# Regulator_9V0_to_5V0.net
KiCad netlist of a schematic drawn in Altium Designer
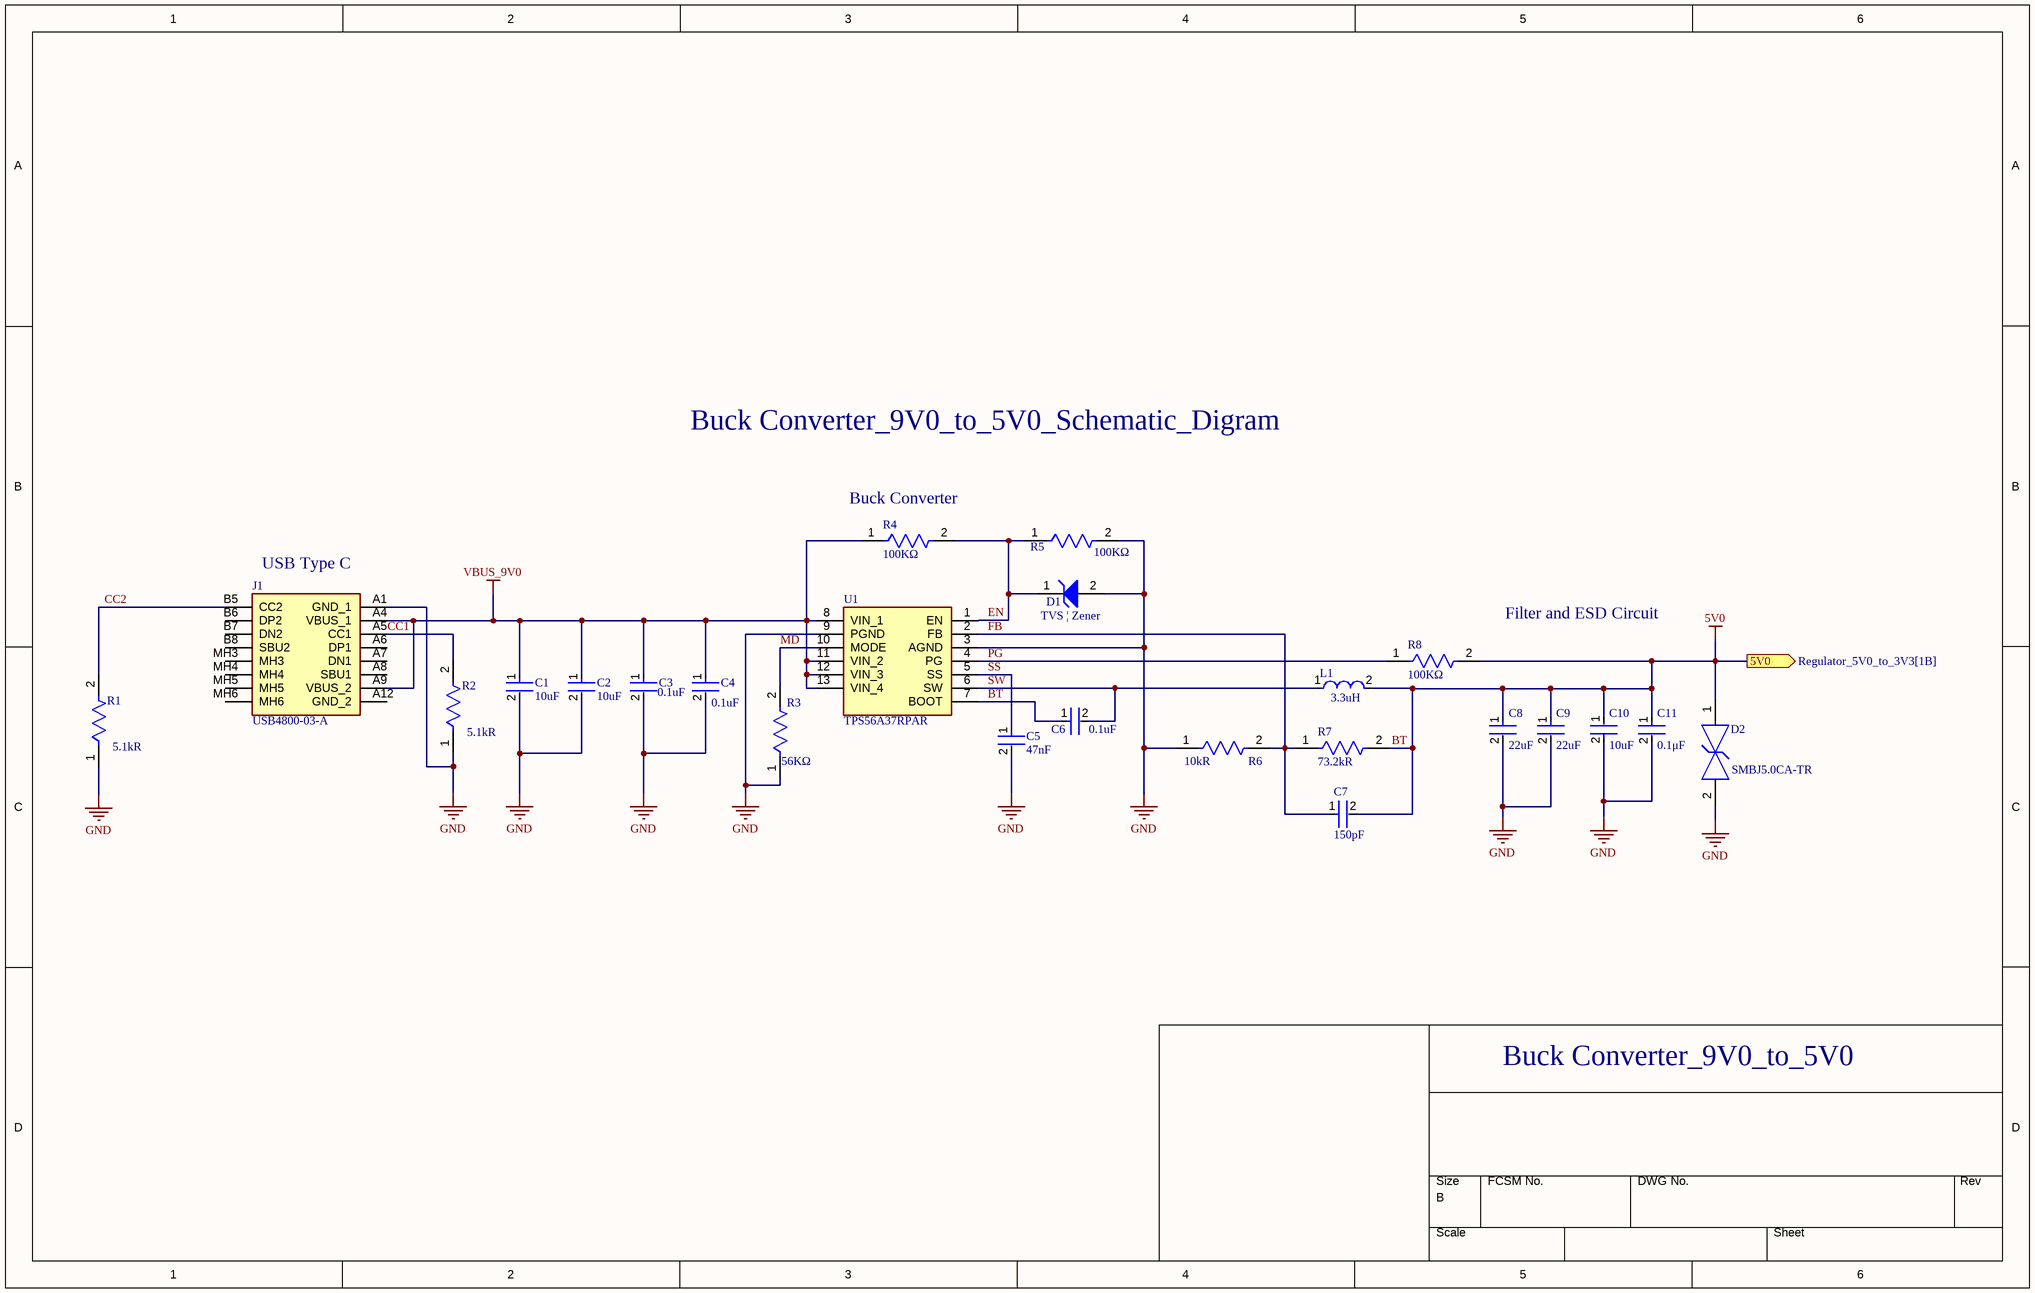
[diagram p0: Regulator_9V0_to_5V0.SchDoc]

(export (version "E")
  (design (tool "Eeschema 10.0.6"))
  (components
    (comp (ref "C1")
      (value "CL21A106KOQNNNG")
      (footprint "FP-CL21-IPC_C")
      (description "CL21 Series 0805 10uF 16V ±10% Tolerance X5R Multilayer Ceramic Chip Capacitor")
      (fields
        (field (name "CAPACITANCE") "10uF")
        (field (name "TOLERANCE") "10%")
        (field (name "VOLTAGE") "16V")
      )
      (libsource (lib "Altium Content Vault") (part "b4654b650e69147ec39a6b967a45e02"))
    )
    (comp (ref "C2")
      (value "CL21A106KOQNNNG")
      (footprint "FP-CL21-IPC_C")
      (description "CL21 Series 0805 10uF 16V ±10% Tolerance X5R Multilayer Ceramic Chip Capacitor")
      (fields
        (field (name "CAPACITANCE") "10uF")
        (field (name "TOLERANCE") "10%")
        (field (name "VOLTAGE") "16V")
      )
      (libsource (lib "Altium Content Vault") (part "b4654b650e69147ec39a6b967a45e02"))
    )
    (comp (ref "C3")
      (value "0402YD104KAT2A")
      (footprint "FP-0402-L_1_0_1-W_0_5_0_1-IPC_B")
      (description "General Purpose Ceramic Capacitor, 0402, 10uF, 10%, X5R, 15%, 16V")
      (fields
        (field (name "VOLTAGE") "16V")
        (field (name "TOLERANCE") "10%")
        (field (name "CAPACITANCE") "0.1uF")
      )
      (libsource (lib "Altium Content Vault") (part "b4654b650e69147ec39a6b967a45e02"))
    )
    (comp (ref "C4")
      (value "0402YD104KAT2A")
      (footprint "FP-0402-L_1_0_1-W_0_5_0_1-IPC_B")
      (description "General Purpose Ceramic Capacitor, 0402, 10uF, 10%, X5R, 15%, 16V")
      (fields
        (field (name "VOLTAGE") "16V")
        (field (name "TOLERANCE") "10%")
        (field (name "CAPACITANCE") "0.1uF")
      )
      (libsource (lib "Altium Content Vault") (part "b4654b650e69147ec39a6b967a45e02"))
    )
    (comp (ref "C5")
      (value "CL05B473KO5NNNC")
      (footprint "FP-CL579-IPC_C")
      (description "Cap Ceramic 47nF 16V X7R ±10% SMD 0402 +125°C Paper T/R")
      (fields
        (field (name "VOLTAGE") "16V")
        (field (name "CAPACITANCE") "47nF")
        (field (name "TOLERANCE") "10%")
      )
      (libsource (lib "Altium Content Vault") (part "b4654b650e69147ec39a6b967a45e02"))
    )
    (comp (ref "C6")
      (value "0402YD104KAT2A")
      (footprint "FP-0402-L_1_0_1-W_0_5_0_1-IPC_B")
      (description "General Purpose Ceramic Capacitor, 0402, 10uF, 10%, X5R, 15%, 16V")
      (fields
        (field (name "VOLTAGE") "16V")
        (field (name "TOLERANCE") "10%")
        (field (name "CAPACITANCE") "0.1uF")
      )
      (libsource (lib "Altium Content Vault") (part "b4654b650e69147ec39a6b967a45e02"))
    )
    (comp (ref "C7")
      (value "C1005NP01H151J050BA")
      (footprint "FP-C1005-050-0_05-IPC_B")
      (description "Multilayer Ceramic Capacitors 150pF ±5% 50V NP0 SMD 0402")
      (fields (field (name "CAPACITANCE") "150pF") (field (name "TOLERANCE") "5%"))
      (libsource (lib "Altium Content Vault") (part "b4654b650e69147ec39a6b967a45e02"))
    )
    (comp (ref "C8")
      (value "CL10A226MO7JZNC")
      (footprint "FP-CL10-IPC_B")
      (description "Cap Ceramic 22uF 16V X5R ±20% Pad SMD 0603 +85°C T/R")
      (fields (field (name "CAPACITANCE") "22uF") (field (name "TOLERANCE") "20%"))
      (libsource (lib "Altium Content Vault") (part "b4654b650e69147ec39a6b967a45e02"))
    )
    (comp (ref "C9")
      (value "CL10A226MO7JZNC")
      (footprint "FP-CL10-IPC_B")
      (description "Cap Ceramic 22uF 16V X5R ±20% Pad SMD 0603 +85°C T/R")
      (fields (field (name "CAPACITANCE") "22uF") (field (name "TOLERANCE") "20%"))
      (libsource (lib "Altium Content Vault") (part "b4654b650e69147ec39a6b967a45e02"))
    )
    (comp (ref "C10")
      (value "C1608X5R1A106M080AC")
      (footprint "FP-C1608-080-0_1-IPC_A")
      (description "Multilayer Ceramic Capacitors 10μF ±20% 10V X5R SMD 0603")
      (fields (field (name "CAPACITANCE") "10uF") (field (name "TOLERANCE") "20%"))
      (libsource (lib "Altium Content Vault") (part "236180d848d6139a670b325ea6854c9"))
    )
    (comp (ref "C11")
      (value "C0603C104K8RACTU")
      (footprint "FP-C0603C-CF-MFG")
      (description "CAP CER 0.1UF 10V X7R 0603")
      (fields
        (field (name "TOLERANCE") "0.1")
        (field (name "OCTOPART") "https://octopart.com/c0603c104k8ractu-kemet-145075")
        (field (name "CAPACITANCE") "0.1μF")
      )
      (libsource (lib "Altium Content Vault") (part "b4654b650e69147ec39a6b967a45e02"))
    )
    (comp (ref "D1")
      (value "ESD5Z6.0T1G")
      (footprint "ONSC-SOD-523-2-502-01_V")
      (fields (field (name "MANUFACTURER") "On Semiconductor"))
      (libsource (lib "Altium Content Vault") (part "ONSC-K1A2-2"))
    )
    (comp (ref "D2")
      (value "SMBJ5.0CA-TR")
      (footprint "FP-SMB-CA-MFG")
      (description "TVS DIODE 5V 13.4V SMB")
      (fields
        (field (name "MANUFACTURER") "STMicroelectronics")
        (field (name "OCTOPART") "https://octopart.com/smbj5.0ca-tr-stmicroelectronics-347080")
      )
      (libsource (lib "Altium Content Vault") (part "876f4347bf90aa6f500f43e3cd03972"))
    )
    (comp (ref "J1")
      (value "USB4800-03-A")
      (footprint "USB480003A")
      (description "Connector")
      (fields (field (name "MOUSER PART NUMBER") "640-USB4800-03-A"))
      (libsource (lib "USB480003A") (part "USB4800-03-A"))
    )
    (comp (ref "L1")
      (value "IHLP2020CZER3R3M11")
      (footprint "FP-IHLP-2020CZ-FP_1_905x2-MFG")
      (description "Fixed Inductors Commercial Low DCR Series 3.3uH 5.5A 40.4mΩ 20%")
      (fields (field (name "INDUCTANCE") "3.3uH") (field (name "TOLERANCE") "20%"))
      (libsource (lib "Altium Content Vault") (part "725321dda6339637d4d059423bc1c3c"))
    )
    (comp (ref "R1")
      (value "CRCW04025K10FKED")
      (footprint "FP-CRCW0402-e3-IPC_C")
      (description "RES Thick Film, 5.1kΩ, 1%, 0.063W, 100ppm/°C, 0402")
      (fields (field (name "TOLERANCE") "1%") (field (name "RESISTANCE") "5.1kR"))
      (libsource (lib "Altium Content Vault") (part "1029c3af85768c4190bb7ad29bc67b5"))
    )
    (comp (ref "R2")
      (value "CRCW04025K10FKED")
      (footprint "FP-CRCW0402-e3-IPC_C")
      (description "RES Thick Film, 5.1kΩ, 1%, 0.063W, 100ppm/°C, 0402")
      (fields (field (name "TOLERANCE") "1%") (field (name "RESISTANCE") "5.1kR"))
      (libsource (lib "Altium Content Vault") (part "1029c3af85768c4190bb7ad29bc67b5"))
    )
    (comp (ref "R3")
      (value "CRGCQ0402F56K")
      (footprint "FP-CRGCQ0402-IPC_C")
      (description "CRGCQ 0402 56K 1%")
      (fields
        (field (name "OCTOPART") "https://octopart.com/crgcq0402f56k-te+connectivity-91017978")
        (field (name "RESISTANCE") "56KΩ")
        (field (name "MANUFACTURER") "TE Connectivity")
      )
      (libsource (lib "Altium Content Vault") (part "1029c3af85768c4190bb7ad29bc67b5"))
    )
    (comp (ref "R4")
      (value "CRGP0402F100K")
      (footprint "FP-CRGP0402-IPC_C")
      (description "SMD Precision Pulse Thick Film Chip Resistor")
      (fields
        (field (name "OCTOPART") "https://octopart.com/crgp0402f100k-te+connectivity-91018658")
        (field (name "TOLERANCE") "0.01")
        (field (name "RESISTANCE") "100KΩ")
      )
      (libsource (lib "Altium Content Vault") (part "1029c3af85768c4190bb7ad29bc67b5"))
    )
    (comp (ref "R5")
      (value "CRGP0402F100K")
      (footprint "FP-CRGP0402-IPC_C")
      (description "SMD Precision Pulse Thick Film Chip Resistor")
      (fields
        (field (name "OCTOPART") "https://octopart.com/crgp0402f100k-te+connectivity-91018658")
        (field (name "TOLERANCE") "0.01")
        (field (name "RESISTANCE") "100KΩ")
      )
      (libsource (lib "Altium Content Vault") (part "1029c3af85768c4190bb7ad29bc67b5"))
    )
    (comp (ref "R6")
      (value "AC0402FR-0710KL")
      (footprint "FP-AC0402-MFG")
      (description "RES 10kΩ ±1% 0.063W 0402")
      (fields (field (name "TOLERANCE") "1%") (field (name "RESISTANCE") "10kR"))
      (libsource (lib "Altium Content Vault") (part "1029c3af85768c4190bb7ad29bc67b5"))
    )
    (comp (ref "R7")
      (value "RC1005F7322CS")
      (footprint "FP-RC1005-IPC_B")
      (description "Res Thick Film 0402 73.2kΩ 1% 0.063W ±100ppm/°C Molded SMD T/R")
      (fields (field (name "TOLERANCE") "1%") (field (name "RESISTANCE") "73.2kR"))
      (libsource (lib "Altium Content Vault") (part "1029c3af85768c4190bb7ad29bc67b5"))
    )
    (comp (ref "R8")
      (value "CRGP0402F100K")
      (footprint "FP-CRGP0402-IPC_C")
      (description "SMD Precision Pulse Thick Film Chip Resistor")
      (fields
        (field (name "OCTOPART") "https://octopart.com/crgp0402f100k-te+connectivity-91018658")
        (field (name "TOLERANCE") "0.01")
        (field (name "RESISTANCE") "100KΩ")
      )
      (libsource (lib "Altium Content Vault") (part "1029c3af85768c4190bb7ad29bc67b5"))
    )
    (comp (ref "U1")
      (value "TPS56A37RPAR")
      (footprint "TPS56A37RPAR")
      (description "Integrated Circuit")
      (fields (field (name "MOUSER PART NUMBER") "595-TPS56A37RPAR"))
      (libsource (lib "TPS56A37RPAR") (part "TPS56A37RPAR"))
    )
  )
  (nets
    (net (code "1") (name "/CC1") (class "Default")
      (node (ref "J1") (pin "A5") (pinfunction "CC1_A5") (pintype "passive"))
      (node (ref "R2") (pin "2") (pinfunction "2_2") (pintype "passive"))
    )
    (net (code "2") (name "/CC2") (class "Default")
      (node (ref "J1") (pin "B5") (pinfunction "CC2_B5") (pintype "passive"))
      (node (ref "R1") (pin "2") (pinfunction "2_2") (pintype "passive"))
    )
    (net (code "3") (name "/EN") (class "Default")
      (node (ref "D1") (pin "1") (pinfunction "K_1") (pintype "passive"))
      (node (ref "R4") (pin "2") (pinfunction "2_2") (pintype "passive"))
      (node (ref "R5") (pin "1") (pinfunction "1_1") (pintype "passive"))
      (node (ref "U1") (pin "1") (pinfunction "EN_1") (pintype "passive"))
    )
    (net (code "4") (name "/FB") (class "Default")
      (node (ref "C7") (pin "1") (pinfunction "1_1") (pintype "passive"))
      (node (ref "R6") (pin "2") (pinfunction "2_2") (pintype "passive"))
      (node (ref "R7") (pin "1") (pinfunction "1_1") (pintype "passive"))
      (node (ref "U1") (pin "2") (pinfunction "FB_2") (pintype "passive"))
    )
    (net (code "5") (name "/MD") (class "Default")
      (node (ref "R3") (pin "2") (pinfunction "2_2") (pintype "passive"))
      (node (ref "U1") (pin "10") (pinfunction "MODE_10") (pintype "passive"))
    )
    (net (code "6") (name "/PG") (class "Default")
      (node (ref "R8") (pin "1") (pinfunction "1_1") (pintype "passive"))
      (node (ref "U1") (pin "4") (pinfunction "PG_4") (pintype "passive"))
    )
    (net (code "7") (name "/SS") (class "Default")
      (node (ref "C5") (pin "1") (pinfunction "1_1") (pintype "passive"))
      (node (ref "U1") (pin "5") (pinfunction "SS_5") (pintype "passive"))
    )
    (net (code "8") (name "/SW") (class "Default")
      (node (ref "C6") (pin "2") (pinfunction "2_2") (pintype "passive"))
      (node (ref "L1") (pin "1") (pinfunction "1_1") (pintype "passive"))
      (node (ref "U1") (pin "6") (pinfunction "SW_6") (pintype "passive"))
    )
    (net (code "9") (name "5V0") (class "Default")
      (node (ref "C10") (pin "1") (pinfunction "1_1") (pintype "passive"))
      (node (ref "C11") (pin "1") (pinfunction "1_1") (pintype "passive"))
      (node (ref "C6") (pin "1") (pinfunction "1_1") (pintype "passive"))
      (node (ref "C7") (pin "2") (pinfunction "2_2") (pintype "passive"))
      (node (ref "C8") (pin "1") (pinfunction "1_1") (pintype "passive"))
      (node (ref "C9") (pin "1") (pinfunction "1_1") (pintype "passive"))
      (node (ref "D2") (pin "1") (pinfunction "1_1") (pintype "passive"))
      (node (ref "L1") (pin "2") (pinfunction "2_2") (pintype "passive"))
      (node (ref "R7") (pin "2") (pinfunction "2_2") (pintype "passive"))
      (node (ref "R8") (pin "2") (pinfunction "2_2") (pintype "passive"))
      (node (ref "U1") (pin "7") (pinfunction "BOOT_7") (pintype "passive"))
    )
    (net (code "10") (name "GND") (class "Default")
      (node (ref "C1") (pin "2") (pinfunction "2_2") (pintype "passive"))
      (node (ref "C10") (pin "2") (pinfunction "2_2") (pintype "passive"))
      (node (ref "C11") (pin "2") (pinfunction "2_2") (pintype "passive"))
      (node (ref "C2") (pin "2") (pinfunction "2_2") (pintype "passive"))
      (node (ref "C3") (pin "2") (pinfunction "2_2") (pintype "passive"))
      (node (ref "C4") (pin "2") (pinfunction "2_2") (pintype "passive"))
      (node (ref "C5") (pin "2") (pinfunction "2_2") (pintype "passive"))
      (node (ref "C8") (pin "2") (pinfunction "2_2") (pintype "passive"))
      (node (ref "C9") (pin "2") (pinfunction "2_2") (pintype "passive"))
      (node (ref "D1") (pin "2") (pinfunction "A_2") (pintype "passive"))
      (node (ref "D2") (pin "2") (pinfunction "2_2") (pintype "passive"))
      (node (ref "J1") (pin "A1") (pinfunction "GND_1_A1") (pintype "passive"))
      (node (ref "R1") (pin "1") (pinfunction "1_1") (pintype "passive"))
      (node (ref "R2") (pin "1") (pinfunction "1_1") (pintype "passive"))
      (node (ref "R3") (pin "1") (pinfunction "1_1") (pintype "passive"))
      (node (ref "R5") (pin "2") (pinfunction "2_2") (pintype "passive"))
      (node (ref "R6") (pin "1") (pinfunction "1_1") (pintype "passive"))
      (node (ref "U1") (pin "3") (pinfunction "AGND_3") (pintype "passive"))
      (node (ref "U1") (pin "9") (pinfunction "PGND_9") (pintype "passive"))
    )
    (net (code "11") (name "VBUS_9V0") (class "Default")
      (node (ref "C1") (pin "1") (pinfunction "1_1") (pintype "passive"))
      (node (ref "C2") (pin "1") (pinfunction "1_1") (pintype "passive"))
      (node (ref "C3") (pin "1") (pinfunction "1_1") (pintype "passive"))
      (node (ref "C4") (pin "1") (pinfunction "1_1") (pintype "passive"))
      (node (ref "J1") (pin "A4") (pinfunction "VBUS_1_A4") (pintype "passive"))
      (node (ref "J1") (pin "A9") (pinfunction "VBUS_2_A9") (pintype "passive"))
      (node (ref "R4") (pin "1") (pinfunction "1_1") (pintype "passive"))
      (node (ref "U1") (pin "11") (pinfunction "VIN_2_11") (pintype "passive"))
      (node (ref "U1") (pin "12") (pinfunction "VIN_3_12") (pintype "passive"))
      (node (ref "U1") (pin "13") (pinfunction "VIN_4_13") (pintype "passive"))
      (node (ref "U1") (pin "8") (pinfunction "VIN_1_8") (pintype "passive"))
    )
    (net (code "12") (name "unconnected-(J1-DN1-PadA7)") (class "Default")
      (node (ref "J1") (pin "A7") (pinfunction "DN1_A7") (pintype "passive"))
    )
    (net (code "13") (name "unconnected-(J1-DN2-PadB7)") (class "Default")
      (node (ref "J1") (pin "B7") (pinfunction "DN2_B7") (pintype "passive"))
    )
    (net (code "14") (name "unconnected-(J1-DP1-PadA6)") (class "Default")
      (node (ref "J1") (pin "A6") (pinfunction "DP1_A6") (pintype "passive"))
    )
    (net (code "15") (name "unconnected-(J1-DP2-PadB6)") (class "Default")
      (node (ref "J1") (pin "B6") (pinfunction "DP2_B6") (pintype "passive"))
    )
    (net (code "16") (name "unconnected-(J1-GND_2-PadA12)") (class "Default")
      (node (ref "J1") (pin "A12") (pinfunction "GND_2_A12") (pintype "passive"))
    )
    (net (code "17") (name "unconnected-(J1-PadMH3)") (class "Default")
      (node (ref "J1") (pin "MH3") (pinfunction "MH3_MH3") (pintype "passive"))
    )
    (net (code "18") (name "unconnected-(J1-PadMH4)") (class "Default")
      (node (ref "J1") (pin "MH4") (pinfunction "MH4_MH4") (pintype "passive"))
    )
    (net (code "19") (name "unconnected-(J1-PadMH5)") (class "Default")
      (node (ref "J1") (pin "MH5") (pinfunction "MH5_MH5") (pintype "passive"))
    )
    (net (code "20") (name "unconnected-(J1-PadMH6)") (class "Default")
      (node (ref "J1") (pin "MH6") (pinfunction "MH6_MH6") (pintype "passive"))
    )
    (net (code "21") (name "unconnected-(J1-SBU1-PadA8)") (class "Default")
      (node (ref "J1") (pin "A8") (pinfunction "SBU1_A8") (pintype "passive"))
    )
    (net (code "22") (name "unconnected-(J1-SBU2-PadB8)") (class "Default")
      (node (ref "J1") (pin "B8") (pinfunction "SBU2_B8") (pintype "passive"))
    )
  )
)
